# knixx_SW4_00.net
KiCad netlist of a schematic drawn in Altium Designer
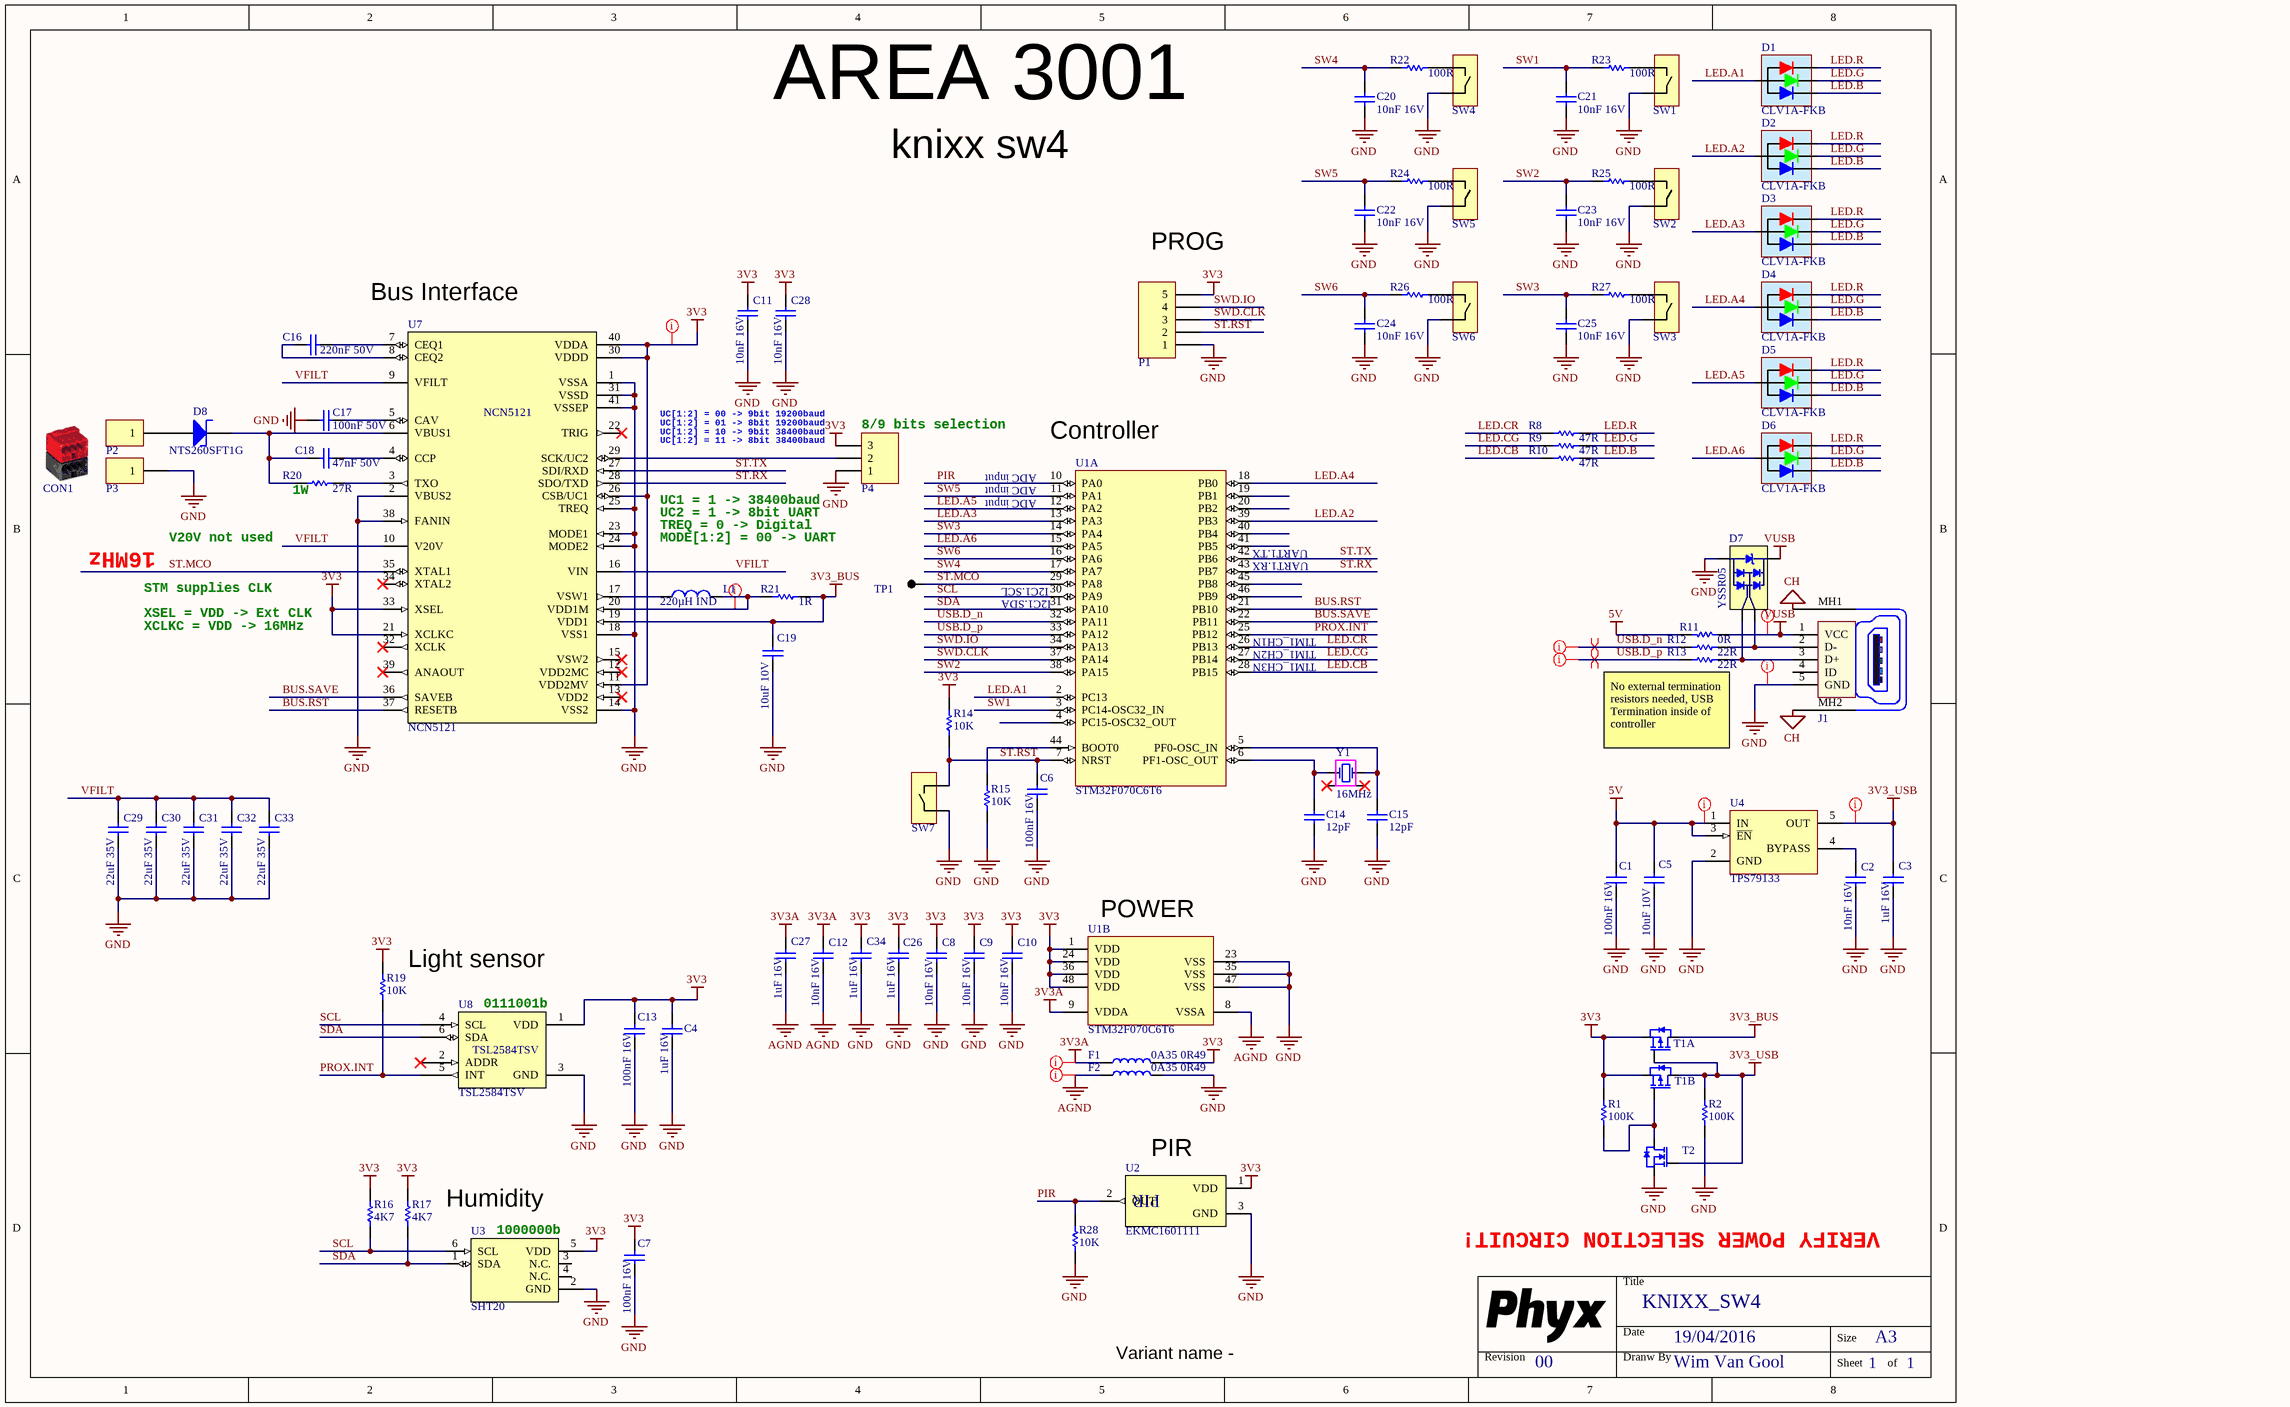
[diagram p0: knixx_SW4_00.SchDoc]

(export (version "E")
  (design (tool "Eeschema 10.0.6"))
  (components
    (comp (ref "C1")
      (value "100nF 16V")
      (footprint "C0402")
      (description "Capacitor Ceramic")
      (fields (field (name "Comment") "CAP_CERAMIC"))
      (libsource (lib "Phyx_Components") (part "CAP_CERAMIC"))
    )
    (comp (ref "C2")
      (value "10nF 16V")
      (footprint "C0402")
      (description "Capacitor Ceramic")
      (fields (field (name "Comment") "CAP_CERAMIC"))
      (libsource (lib "Phyx_Components") (part "CAP_CERAMIC"))
    )
    (comp (ref "C3")
      (value "1uF 16V")
      (footprint "C0603_N")
      (description "Capacitor Ceramic")
      (fields (field (name "Comment") "CAP_CERAMIC"))
      (libsource (lib "Phyx_Components") (part "CAP_CERAMIC"))
    )
    (comp (ref "C4")
      (value "1uF 16V")
      (footprint "C0603_N")
      (description "Capacitor Ceramic")
      (fields (field (name "Comment") "CAP_CERAMIC"))
      (libsource (lib "Phyx_Components") (part "CAP_CERAMIC"))
    )
    (comp (ref "C5")
      (value "10uF 10V")
      (footprint "C0805_N")
      (description "Capacitor Ceramic")
      (fields (field (name "Comment") "CAP_CERAMIC"))
      (libsource (lib "Phyx_Components") (part "CAP_CERAMIC"))
    )
    (comp (ref "C6")
      (value "100nF 16V")
      (footprint "C0402")
      (description "Capacitor Ceramic")
      (fields (field (name "Comment") "CAP_CERAMIC"))
      (libsource (lib "Phyx_Components") (part "CAP_CERAMIC"))
    )
    (comp (ref "C7")
      (value "100nF 16V")
      (footprint "C0402")
      (description "Capacitor Ceramic")
      (fields (field (name "Comment") "CAP_CERAMIC"))
      (libsource (lib "Phyx_Components") (part "CAP_CERAMIC"))
    )
    (comp (ref "C8")
      (value "10nF 16V")
      (footprint "C0402")
      (description "Capacitor Ceramic")
      (fields (field (name "Comment") "CAP_CERAMIC"))
      (libsource (lib "Phyx_Components") (part "CAP_CERAMIC"))
    )
    (comp (ref "C9")
      (value "10nF 16V")
      (footprint "C0402")
      (description "Capacitor Ceramic")
      (fields (field (name "Comment") "CAP_CERAMIC"))
      (libsource (lib "Phyx_Components") (part "CAP_CERAMIC"))
    )
    (comp (ref "C10")
      (value "10nF 16V")
      (footprint "C0402")
      (description "Capacitor Ceramic")
      (fields (field (name "Comment") "CAP_CERAMIC"))
      (libsource (lib "Phyx_Components") (part "CAP_CERAMIC"))
    )
    (comp (ref "C11")
      (value "10nF 16V")
      (footprint "C0402")
      (description "Capacitor Ceramic")
      (fields (field (name "Comment") "CAP_CERAMIC"))
      (libsource (lib "Phyx_Components") (part "CAP_CERAMIC"))
    )
    (comp (ref "C12")
      (value "10nF 16V")
      (footprint "C0402")
      (description "Capacitor Ceramic")
      (fields (field (name "Comment") "CAP_CERAMIC"))
      (libsource (lib "Phyx_Components") (part "CAP_CERAMIC"))
    )
    (comp (ref "C13")
      (value "100nF 16V")
      (footprint "C0402")
      (description "Capacitor Ceramic")
      (fields (field (name "Comment") "CAP_CERAMIC"))
      (libsource (lib "Phyx_Components") (part "CAP_CERAMIC"))
    )
    (comp (ref "C14")
      (value "12pF")
      (footprint "C0402")
      (description "Capacitor Ceramic")
      (fields (field (name "Comment") "CAP_CERAMIC"))
      (libsource (lib "Phyx_Components") (part "CAP_CERAMIC"))
    )
    (comp (ref "C15")
      (value "12pF")
      (footprint "C0402")
      (description "Capacitor Ceramic")
      (fields (field (name "Comment") "CAP_CERAMIC"))
      (libsource (lib "Phyx_Components") (part "CAP_CERAMIC"))
    )
    (comp (ref "C16")
      (value "220nF 50V")
      (footprint "C0805_N")
      (description "Capacitor Ceramic")
      (fields (field (name "Comment") "CAP_CERAMIC"))
      (libsource (lib "Phyx_Components") (part "CAP_CERAMIC"))
    )
    (comp (ref "C17")
      (value "100nF 50V")
      (footprint "C0603_N")
      (description "Capacitor Ceramic")
      (fields (field (name "Comment") "CAP_CERAMIC"))
      (libsource (lib "Phyx_Components") (part "CAP_CERAMIC"))
    )
    (comp (ref "C18")
      (value "47nF 50V")
      (footprint "C0603_N")
      (description "Capacitor Ceramic")
      (fields (field (name "Comment") "CAP_CERAMIC"))
      (libsource (lib "Phyx_Components") (part "CAP_CERAMIC"))
    )
    (comp (ref "C19")
      (value "10uF 10V")
      (footprint "C0805_N")
      (description "Capacitor Ceramic")
      (fields (field (name "Comment") "CAP_CERAMIC"))
      (libsource (lib "Phyx_Components") (part "CAP_CERAMIC"))
    )
    (comp (ref "C20")
      (value "10nF 16V")
      (footprint "C0402")
      (description "Capacitor Ceramic")
      (fields (field (name "Comment") "CAP_CERAMIC"))
      (libsource (lib "Phyx_Components") (part "CAP_CERAMIC"))
    )
    (comp (ref "C21")
      (value "10nF 16V")
      (footprint "C0402")
      (description "Capacitor Ceramic")
      (fields (field (name "Comment") "CAP_CERAMIC"))
      (libsource (lib "Phyx_Components") (part "CAP_CERAMIC"))
    )
    (comp (ref "C22")
      (value "10nF 16V")
      (footprint "C0402")
      (description "Capacitor Ceramic")
      (fields (field (name "Comment") "CAP_CERAMIC"))
      (libsource (lib "Phyx_Components") (part "CAP_CERAMIC"))
    )
    (comp (ref "C23")
      (value "10nF 16V")
      (footprint "C0402")
      (description "Capacitor Ceramic")
      (fields (field (name "Comment") "CAP_CERAMIC"))
      (libsource (lib "Phyx_Components") (part "CAP_CERAMIC"))
    )
    (comp (ref "C24")
      (value "10nF 16V")
      (footprint "C0402")
      (description "Capacitor Ceramic")
      (fields (field (name "Comment") "CAP_CERAMIC"))
      (libsource (lib "Phyx_Components") (part "CAP_CERAMIC"))
    )
    (comp (ref "C25")
      (value "10nF 16V")
      (footprint "C0402")
      (description "Capacitor Ceramic")
      (fields (field (name "Comment") "CAP_CERAMIC"))
      (libsource (lib "Phyx_Components") (part "CAP_CERAMIC"))
    )
    (comp (ref "C26")
      (value "1uF 16V")
      (footprint "C0603_N")
      (description "CAP # 1uF 16V 0603")
      (fields (field (name "Comment") "CAP_CERAMIC"))
      (libsource (lib "Phyx_Components") (part "CAP_CERAMIC"))
    )
    (comp (ref "C27")
      (value "1uF 16V")
      (footprint "C0603_N")
      (description "Capacitor Ceramic")
      (fields (field (name "Comment") "CAP_CERAMIC"))
      (libsource (lib "Phyx_Components") (part "CAP_CERAMIC"))
    )
    (comp (ref "C28")
      (value "10nF 16V")
      (footprint "C0402")
      (description "Capacitor Ceramic")
      (fields (field (name "Comment") "CAP_CERAMIC"))
      (libsource (lib "Phyx_Components") (part "CAP_CERAMIC"))
    )
    (comp (ref "C29")
      (value "22uF 35V")
      (footprint "C1206_N")
      (description "CAP # 22uF 35V 1206 X5R")
      (fields (field (name "Comment") "CAP_CERAMIC"))
      (libsource (lib "Phyx_Components") (part "CAP_CERAMIC"))
    )
    (comp (ref "C30")
      (value "22uF 35V")
      (footprint "C1206_N")
      (description "CAP # 22uF 35V 1206 X5R")
      (fields (field (name "Comment") "CAP_CERAMIC"))
      (libsource (lib "Phyx_Components") (part "CAP_CERAMIC"))
    )
    (comp (ref "C31")
      (value "22uF 35V")
      (footprint "C1206_N")
      (description "CAP # 22uF 35V 1206 X5R")
      (fields (field (name "Comment") "CAP_CERAMIC"))
      (libsource (lib "Phyx_Components") (part "CAP_CERAMIC"))
    )
    (comp (ref "C32")
      (value "22uF 35V")
      (footprint "C1206_N")
      (description "CAP # 22uF 35V 1206 X5R")
      (fields (field (name "Comment") "CAP_CERAMIC"))
      (libsource (lib "Phyx_Components") (part "CAP_CERAMIC"))
    )
    (comp (ref "C33")
      (value "22uF 35V")
      (footprint "C1206_N")
      (description "CAP # 22uF 35V 1206 X5R")
      (fields (field (name "Comment") "CAP_CERAMIC"))
      (libsource (lib "Phyx_Components") (part "CAP_CERAMIC"))
    )
    (comp (ref "C34")
      (value "1uF 16V")
      (footprint "C0603_N")
      (description "Capacitor Ceramic")
      (fields (field (name "Comment") "CAP_CERAMIC"))
      (libsource (lib "Phyx_Components") (part "CAP_CERAMIC"))
    )
    (comp (ref "CON1")
      (value "CONNECTOR FOR EIB APPLICATIONS PUSH-WIRE® CONNECTION")
      (footprint "WAGO_243-211")
      (libsource (lib "Phyx_Components") (part "WAGO_243-211"))
    )
    (comp (ref "D1")
      (value "CLV1A-FKB")
      (footprint "Cree_CLV1A-FKB")
      (description "=Description")
      (fields (field (name "Comment") "PLCC2 general purpose RGB LED Cree CLV1A-FKB"))
      (libsource (lib "Phyx_Components") (part "Cree_CLV1A-FKB"))
    )
    (comp (ref "D2")
      (value "CLV1A-FKB")
      (footprint "Cree_CLV1A-FKB")
      (description "=Description")
      (fields (field (name "Comment") "PLCC2 general purpose RGB LED Cree CLV1A-FKB"))
      (libsource (lib "Phyx_Components") (part "Cree_CLV1A-FKB"))
    )
    (comp (ref "D3")
      (value "CLV1A-FKB")
      (footprint "Cree_CLV1A-FKB")
      (description "=Description")
      (fields (field (name "Comment") "PLCC2 general purpose RGB LED Cree CLV1A-FKB"))
      (libsource (lib "Phyx_Components") (part "Cree_CLV1A-FKB"))
    )
    (comp (ref "D4")
      (value "CLV1A-FKB")
      (footprint "Cree_CLV1A-FKB")
      (description "=Description")
      (fields (field (name "Comment") "PLCC2 general purpose RGB LED Cree CLV1A-FKB"))
      (libsource (lib "Phyx_Components") (part "Cree_CLV1A-FKB"))
    )
    (comp (ref "D5")
      (value "CLV1A-FKB")
      (footprint "Cree_CLV1A-FKB")
      (description "=Description")
      (fields (field (name "Comment") "PLCC2 general purpose RGB LED Cree CLV1A-FKB"))
      (libsource (lib "Phyx_Components") (part "Cree_CLV1A-FKB"))
    )
    (comp (ref "D6")
      (value "CLV1A-FKB")
      (footprint "Cree_CLV1A-FKB")
      (description "=Description")
      (fields (field (name "Comment") "PLCC2 general purpose RGB LED Cree CLV1A-FKB"))
      (libsource (lib "Phyx_Components") (part "Cree_CLV1A-FKB"))
    )
    (comp (ref "D7")
      (value "YSSR05")
      (footprint "SOT-143")
      (description "=Description")
      (fields (field (name "Comment") "Low Capacitanse TVS Diode array"))
      (libsource (lib "Phyx_Components") (part "YSSR05"))
    )
    (comp (ref "D8")
      (value "NTS260SFT1G")
      (footprint "ON_SOD-123FL")
      (description "=Description")
      (fields (field (name "Comment") "NTS260SFT1G  Schottky Rectifier, Single, 60 V, 2 A, SOD-123, 650 mV"))
      (libsource (lib "Phyx_Components") (part "Schottky_21"))
    )
    (comp (ref "F1")
      (value "0A35 0R49")
      (footprint "L0402")
      (fields (field (name "Comment") "BLM15AX102SN1D"))
      (libsource (lib "Phyx_Components") (part "FERRITE"))
    )
    (comp (ref "F2")
      (value "0A35 0R49")
      (footprint "L0402")
      (fields (field (name "Comment") "BLM15AX102SN1D"))
      (libsource (lib "Phyx_Components") (part "FERRITE"))
    )
    (comp (ref "J1")
      (value "Vertical Micro USB B 614105150721")
      (footprint "WE_614105150721")
      (libsource (lib "Phyx_Components") (part "WE_614105150721"))
    )
    (comp (ref "L1")
      (value "220µH IND")
      (footprint "IND_6045")
      (fields (field (name "Comment") "220µH INDUCTOR"))
      (libsource (lib "Phyx_Components") (part "INDUCTOR"))
    )
    (comp (ref "P1")
      (value "Header 1.0mm Shrouded 5")
      (footprint "WE_665305124022")
      (libsource (lib "Phyx_Components") (part "Header 5"))
    )
    (comp (ref "P2")
      (value "SOLDER PIN FOR PCBS UP TO 2 MM")
      (footprint "WAGO_243-131")
      (libsource (lib "Phyx_Components") (part "Header 1"))
    )
    (comp (ref "P3")
      (value "SOLDER PIN FOR PCBS UP TO 2 MM")
      (footprint "WAGO_243-131")
      (libsource (lib "Phyx_Components") (part "Header 1"))
    )
    (comp (ref "P4")
      (value "3 pin Solder SW Circular 1mm")
      (footprint "SOLDER_SW_C_1MM_3")
      (libsource (lib "Phyx_Components") (part "Header 3"))
    )
    (comp (ref "R1")
      (value "100K")
      (footprint "R0402")
      (fields (field (name "Comment") "RESISTOR"))
      (libsource (lib "Phyx_Components") (part "RESISTOR"))
    )
    (comp (ref "R2")
      (value "100K")
      (footprint "R0402")
      (fields (field (name "Comment") "RESISTOR"))
      (libsource (lib "Phyx_Components") (part "RESISTOR"))
    )
    (comp (ref "R8")
      (value "47R")
      (footprint "R0402")
      (fields (field (name "Comment") "RESISTOR"))
      (libsource (lib "Phyx_Components") (part "RESISTOR"))
    )
    (comp (ref "R9")
      (value "47R")
      (footprint "R0402")
      (fields (field (name "Comment") "RESISTOR"))
      (libsource (lib "Phyx_Components") (part "RESISTOR"))
    )
    (comp (ref "R10")
      (value "47R")
      (footprint "R0402")
      (fields (field (name "Comment") "RESISTOR"))
      (libsource (lib "Phyx_Components") (part "RESISTOR"))
    )
    (comp (ref "R11")
      (value "0R")
      (footprint "R0603_N")
      (fields (field (name "Comment") "RESISTOR"))
      (libsource (lib "Phyx_Components") (part "RESISTOR"))
    )
    (comp (ref "R12")
      (value "22R")
      (footprint "R0402")
      (fields (field (name "Comment") "RESISTOR"))
      (libsource (lib "Phyx_Components") (part "RESISTOR"))
    )
    (comp (ref "R13")
      (value "22R")
      (footprint "R0402")
      (fields (field (name "Comment") "RESISTOR"))
      (libsource (lib "Phyx_Components") (part "RESISTOR"))
    )
    (comp (ref "R14")
      (value "10K")
      (footprint "R0402")
      (fields (field (name "Comment") "RESISTOR"))
      (libsource (lib "Phyx_Components") (part "RESISTOR"))
    )
    (comp (ref "R15")
      (value "10K")
      (footprint "R0402")
      (fields (field (name "Comment") "RESISTOR"))
      (libsource (lib "Phyx_Components") (part "RESISTOR"))
    )
    (comp (ref "R16")
      (value "4K7")
      (footprint "R0402")
      (fields (field (name "Comment") "RESISTOR"))
      (libsource (lib "Phyx_Components") (part "RESISTOR"))
    )
    (comp (ref "R17")
      (value "4K7")
      (footprint "R0402")
      (fields (field (name "Comment") "RESISTOR"))
      (libsource (lib "Phyx_Components") (part "RESISTOR"))
    )
    (comp (ref "R19")
      (value "10K")
      (footprint "R0402")
      (fields (field (name "Comment") "RESISTOR"))
      (libsource (lib "Phyx_Components") (part "RESISTOR"))
    )
    (comp (ref "R20")
      (value "27R")
      (footprint "R2512")
      (fields (field (name "Comment") "RESISTOR"))
      (libsource (lib "Phyx_Components") (part "RESISTOR"))
    )
    (comp (ref "R21")
      (value "1R")
      (footprint "R0402")
      (fields (field (name "Comment") "RESISTOR"))
      (libsource (lib "Phyx_Components") (part "RESISTOR"))
    )
    (comp (ref "R22")
      (value "100R")
      (footprint "R0402")
      (fields (field (name "Comment") "RESISTOR"))
      (libsource (lib "Phyx_Components") (part "RESISTOR"))
    )
    (comp (ref "R23")
      (value "100R")
      (footprint "R0402")
      (fields (field (name "Comment") "RESISTOR"))
      (libsource (lib "Phyx_Components") (part "RESISTOR"))
    )
    (comp (ref "R24")
      (value "100R")
      (footprint "R0402")
      (fields (field (name "Comment") "RESISTOR"))
      (libsource (lib "Phyx_Components") (part "RESISTOR"))
    )
    (comp (ref "R25")
      (value "100R")
      (footprint "R0402")
      (fields (field (name "Comment") "RESISTOR"))
      (libsource (lib "Phyx_Components") (part "RESISTOR"))
    )
    (comp (ref "R26")
      (value "100R")
      (footprint "R0402")
      (fields (field (name "Comment") "RESISTOR"))
      (libsource (lib "Phyx_Components") (part "RESISTOR"))
    )
    (comp (ref "R27")
      (value "100R")
      (footprint "R0402")
      (fields (field (name "Comment") "RESISTOR"))
      (libsource (lib "Phyx_Components") (part "RESISTOR"))
    )
    (comp (ref "R28")
      (value "10K")
      (footprint "R0402")
      (fields (field (name "Comment") "RESISTOR"))
      (libsource (lib "Phyx_Components") (part "RESISTOR"))
    )
    (comp (ref "SW1")
      (value "Sealed Tact Switch for SMT 6,2x6,2x7,7")
      (footprint "CK_KSC6xxJ")
      (libsource (lib "Phyx_Components") (part "SW_TACT"))
    )
    (comp (ref "SW2")
      (value "Sealed Tact Switch for SMT 6,2x6,2x7,7")
      (footprint "CK_KSC6xxJ")
      (libsource (lib "Phyx_Components") (part "SW_TACT"))
    )
    (comp (ref "SW3")
      (value "Sealed Tact Switch for SMT 6,2x6,2x7,7")
      (footprint "CK_KSC6xxJ")
      (libsource (lib "Phyx_Components") (part "SW_TACT"))
    )
    (comp (ref "SW4")
      (value "Sealed Tact Switch for SMT 6,2x6,2x7,7")
      (footprint "CK_KSC6xxJ")
      (libsource (lib "Phyx_Components") (part "SW_TACT"))
    )
    (comp (ref "SW5")
      (value "Sealed Tact Switch for SMT 6,2x6,2x7,7")
      (footprint "CK_KSC6xxJ")
      (libsource (lib "Phyx_Components") (part "SW_TACT"))
    )
    (comp (ref "SW6")
      (value "Sealed Tact Switch for SMT 6,2x6,2x7,7")
      (footprint "CK_KSC6xxJ")
      (libsource (lib "Phyx_Components") (part "SW_TACT"))
    )
    (comp (ref "SW7") (value "LP SMD tact sw") (footprint "CK_KMR4") (libsource (lib "") (part "SW_TACT_1")))
    (comp (ref "T1")
      (value "0.8A Dual P-Ch MOSGET Vgs -1.2")
      (footprint "SOT-363")
      (description "=Description")
      (libsource (lib "Phyx_Components") (part "P_MOSFET_S1G1D2S2G2D1"))
    )
    (comp (ref "T2")
      (value "0.2A N-Ch MOSFET Vgs 3.2")
      (footprint "SOT23-3")
      (libsource (lib "Phyx_Components") (part "N_MOSFET_GSD"))
    )
    (comp (ref "TP1")
      (value "TEST_PAD")
      (footprint "TP_0.8mm")
      (libsource (lib "Phyx_Components") (part "TEST_PAD"))
    )
    (comp (ref "U1")
      (value "STM32F070C6T6")
      (footprint "STM_LQFP48_N")
      (description "=Description")
      (fields
        (field (name "PARTNUMBER") "STM32F373CCT6")
        (field (name "Comment") "Entry-level ARM Cortex-M0 Value line MCU with up to 32 Kbytes Flash, 48 MHz CPU, USB")
      )
      (libsource (lib "Phyx_Components") (part "STM32F070C6T6"))
    )
    (comp (ref "U2")
      (value "EKMC1601111")
      (footprint "PAN_EKMC1601111")
      (description "=Description")
      (fields (field (name "Comment") "PIR 5m White"))
      (libsource (lib "Phyx_Components") (part "EKMC160x111x"))
    )
    (comp (ref "U3")
      (value "SHT20")
      (footprint "SNS_DFN6")
      (description "=Description")
      (fields (field (name "Comment") "Sensirion SHT20 temperature and humidity sensor I2C"))
      (libsource (lib "Phyx_Components") (part "SHT2x"))
    )
    (comp (ref "U4")
      (value "TPS79133")
      (footprint "TI_DBV_R-PDSO-G5")
      (description "=Description")
      (fields (field (name "Comment") "3V3 100mA Ultra Low Noise LDO"))
      (libsource (lib "Phyx_Components") (part "TPS791xx"))
    )
    (comp (ref "U7")
      (value "NCN5121")
      (footprint "ONS_QFN40_6x6")
      (description "=Description")
      (fields (field (name "Comment") "KNX Transceiver for Twisted Pair Networks"))
      (libsource (lib "Phyx_Components") (part "NCN5121"))
    )
    (comp (ref "U8")
      (value "TSL2584TSV")
      (footprint "AMS_6TSV")
      (description "=Description")
      (fields (field (name "Comment") "TSL2584TSV Light-to-Digital Device"))
      (libsource (lib "Phyx_Components") (part "TSL2584TSV"))
    )
    (comp (ref "Y1")
      (value "16MHz")
      (footprint "ABMM2")
      (description "XTAL # 16Mhz ABMM2")
      (fields (field (name "Comment") "16MHZ ABMM2"))
      (libsource (lib "Phyx_Components") (part "XTAL_4"))
    )
  )
  (nets
    (net (code "1") (name "/BUS.RST") (class "Default")
      (node (ref "U1") (pin "21") (pinfunction "PB10_21") (pintype "bidirectional"))
      (node (ref "U7") (pin "37") (pinfunction "RESETB_37") (pintype "output"))
    )
    (net (code "2") (name "/BUS.SAVE") (class "Default")
      (node (ref "U1") (pin "22") (pinfunction "PB11_22") (pintype "bidirectional"))
      (node (ref "U7") (pin "36") (pinfunction "SAVEB_36") (pintype "output"))
    )
    (net (code "3") (name "/LED.A1") (class "Default")
      (node (ref "D1") (pin "2") (pinfunction "A_2") (pintype "passive"))
      (node (ref "U1") (pin "2") (pinfunction "PC13_2") (pintype "bidirectional"))
    )
    (net (code "4") (name "/LED.A2") (class "Default")
      (node (ref "D2") (pin "2") (pinfunction "A_2") (pintype "passive"))
      (node (ref "U1") (pin "39") (pinfunction "PB3_39") (pintype "bidirectional"))
    )
    (net (code "5") (name "/LED.A3") (class "Default")
      (node (ref "D3") (pin "2") (pinfunction "A_2") (pintype "passive"))
      (node (ref "U1") (pin "13") (pinfunction "PA3_13") (pintype "bidirectional"))
    )
    (net (code "6") (name "/LED.A4") (class "Default")
      (node (ref "D4") (pin "2") (pinfunction "A_2") (pintype "passive"))
      (node (ref "U1") (pin "18") (pinfunction "PB0_18") (pintype "bidirectional"))
    )
    (net (code "7") (name "/LED.A5") (class "Default")
      (node (ref "D5") (pin "2") (pinfunction "A_2") (pintype "passive"))
      (node (ref "U1") (pin "12") (pinfunction "PA2_12") (pintype "bidirectional"))
    )
    (net (code "8") (name "/LED.A6") (class "Default")
      (node (ref "D6") (pin "2") (pinfunction "A_2") (pintype "passive"))
      (node (ref "U1") (pin "15") (pinfunction "PA5_15") (pintype "bidirectional"))
    )
    (net (code "9") (name "/LED.B") (class "Default")
      (node (ref "D1") (pin "3") (pinfunction "BC_3") (pintype "passive"))
      (node (ref "D2") (pin "3") (pinfunction "BC_3") (pintype "passive"))
      (node (ref "D3") (pin "3") (pinfunction "BC_3") (pintype "passive"))
      (node (ref "D4") (pin "3") (pinfunction "BC_3") (pintype "passive"))
      (node (ref "D5") (pin "3") (pinfunction "BC_3") (pintype "passive"))
      (node (ref "D6") (pin "3") (pinfunction "BC_3") (pintype "passive"))
      (node (ref "R10") (pin "1") (pinfunction "1_1") (pintype "passive"))
    )
    (net (code "10") (name "/LED.CB") (class "Default")
      (node (ref "R10") (pin "2") (pinfunction "2_2") (pintype "passive"))
      (node (ref "U1") (pin "28") (pinfunction "PB15_28") (pintype "bidirectional"))
    )
    (net (code "11") (name "/LED.CG") (class "Default")
      (node (ref "R9") (pin "2") (pinfunction "2_2") (pintype "passive"))
      (node (ref "U1") (pin "27") (pinfunction "PB14_27") (pintype "bidirectional"))
    )
    (net (code "12") (name "/LED.CR") (class "Default")
      (node (ref "R8") (pin "2") (pinfunction "2_2") (pintype "passive"))
      (node (ref "U1") (pin "26") (pinfunction "PB13_26") (pintype "bidirectional"))
    )
    (net (code "13") (name "/LED.G") (class "Default")
      (node (ref "D1") (pin "4") (pinfunction "GC_4") (pintype "passive"))
      (node (ref "D2") (pin "4") (pinfunction "GC_4") (pintype "passive"))
      (node (ref "D3") (pin "4") (pinfunction "GC_4") (pintype "passive"))
      (node (ref "D4") (pin "4") (pinfunction "GC_4") (pintype "passive"))
      (node (ref "D5") (pin "4") (pinfunction "GC_4") (pintype "passive"))
      (node (ref "D6") (pin "4") (pinfunction "GC_4") (pintype "passive"))
      (node (ref "R9") (pin "1") (pinfunction "1_1") (pintype "passive"))
    )
    (net (code "14") (name "/LED.R") (class "Default")
      (node (ref "D1") (pin "1") (pinfunction "RC_1") (pintype "passive"))
      (node (ref "D2") (pin "1") (pinfunction "RC_1") (pintype "passive"))
      (node (ref "D3") (pin "1") (pinfunction "RC_1") (pintype "passive"))
      (node (ref "D4") (pin "1") (pinfunction "RC_1") (pintype "passive"))
      (node (ref "D5") (pin "1") (pinfunction "RC_1") (pintype "passive"))
      (node (ref "D6") (pin "1") (pinfunction "RC_1") (pintype "passive"))
      (node (ref "R8") (pin "1") (pinfunction "1_1") (pintype "passive"))
    )
    (net (code "15") (name "/PIR") (class "Default")
      (node (ref "R28") (pin "1") (pinfunction "1_1") (pintype "passive"))
      (node (ref "U1") (pin "10") (pinfunction "PA0_10") (pintype "bidirectional"))
      (node (ref "U2") (pin "2") (pinfunction "OUT_2") (pintype "output"))
    )
    (net (code "16") (name "/PROX.INT") (class "Default")
      (node (ref "R19") (pin "2") (pinfunction "2_2") (pintype "passive"))
      (node (ref "U1") (pin "25") (pinfunction "PB12_25") (pintype "bidirectional"))
      (node (ref "U8") (pin "5") (pinfunction "INT_5") (pintype "output"))
    )
    (net (code "17") (name "/SCL") (class "Default")
      (node (ref "R16") (pin "2") (pinfunction "2_2") (pintype "passive"))
      (node (ref "U1") (pin "30") (pinfunction "PA9_30") (pintype "bidirectional"))
      (node (ref "U3") (pin "6") (pinfunction "SCL_6") (pintype "input"))
      (node (ref "U8") (pin "4") (pinfunction "SCL_4") (pintype "input"))
    )
    (net (code "18") (name "/SDA") (class "Default")
      (node (ref "R17") (pin "2") (pinfunction "2_2") (pintype "passive"))
      (node (ref "U1") (pin "31") (pinfunction "PA10_31") (pintype "bidirectional"))
      (node (ref "U3") (pin "1") (pinfunction "SDA_1") (pintype "bidirectional"))
      (node (ref "U8") (pin "6") (pinfunction "SDA_6") (pintype "bidirectional"))
    )
    (net (code "19") (name "/ST.MCO") (class "Default")
      (node (ref "TP1") (pin "1") (pinfunction "1_1") (pintype "passive"))
      (node (ref "U1") (pin "29") (pinfunction "PA8_29") (pintype "bidirectional"))
      (node (ref "U7") (pin "35") (pinfunction "XTAL1_35") (pintype "bidirectional"))
    )
    (net (code "20") (name "/ST.RST") (class "Default")
      (node (ref "C6") (pin "1") (pinfunction "1_1") (pintype "passive"))
      (node (ref "P1") (pin "2") (pinfunction "2_2") (pintype "passive"))
      (node (ref "R14") (pin "2") (pinfunction "2_2") (pintype "passive"))
      (node (ref "SW7") (pin "1") (pinfunction "1_1") (pintype "passive"))
      (node (ref "U1") (pin "7") (pinfunction "NRST_7") (pintype "bidirectional"))
    )
    (net (code "21") (name "/ST.RX") (class "Default")
      (node (ref "U1") (pin "43") (pinfunction "PB7_43") (pintype "bidirectional"))
      (node (ref "U7") (pin "28") (pinfunction "SDO/TXD_28") (pintype "output"))
    )
    (net (code "22") (name "/ST.TX") (class "Default")
      (node (ref "U1") (pin "42") (pinfunction "PB6_42") (pintype "bidirectional"))
      (node (ref "U7") (pin "27") (pinfunction "SDI/RXD_27") (pintype "input"))
    )
    (net (code "23") (name "/SW1") (class "Default")
      (node (ref "C21") (pin "1") (pinfunction "1_1") (pintype "passive"))
      (node (ref "R23") (pin "2") (pinfunction "2_2") (pintype "passive"))
      (node (ref "U1") (pin "3") (pinfunction "PC14-OSC32_IN_3") (pintype "bidirectional"))
    )
    (net (code "24") (name "/SW2") (class "Default")
      (node (ref "C23") (pin "1") (pinfunction "1_1") (pintype "passive"))
      (node (ref "R25") (pin "2") (pinfunction "2_2") (pintype "passive"))
      (node (ref "U1") (pin "38") (pinfunction "PA15_38") (pintype "bidirectional"))
    )
    (net (code "25") (name "/SW3") (class "Default")
      (node (ref "C25") (pin "1") (pinfunction "1_1") (pintype "passive"))
      (node (ref "R27") (pin "2") (pinfunction "2_2") (pintype "passive"))
      (node (ref "U1") (pin "14") (pinfunction "PA4_14") (pintype "bidirectional"))
    )
    (net (code "26") (name "/SW4") (class "Default")
      (node (ref "C20") (pin "1") (pinfunction "1_1") (pintype "passive"))
      (node (ref "R22") (pin "2") (pinfunction "2_2") (pintype "passive"))
      (node (ref "U1") (pin "17") (pinfunction "PA7_17") (pintype "bidirectional"))
    )
    (net (code "27") (name "/SW5") (class "Default")
      (node (ref "C22") (pin "1") (pinfunction "1_1") (pintype "passive"))
      (node (ref "R24") (pin "2") (pinfunction "2_2") (pintype "passive"))
      (node (ref "U1") (pin "11") (pinfunction "PA1_11") (pintype "bidirectional"))
    )
    (net (code "28") (name "/SW6") (class "Default")
      (node (ref "C24") (pin "1") (pinfunction "1_1") (pintype "passive"))
      (node (ref "R26") (pin "2") (pinfunction "2_2") (pintype "passive"))
      (node (ref "U1") (pin "16") (pinfunction "PA6_16") (pintype "bidirectional"))
    )
    (net (code "29") (name "/SWD.CLK") (class "Default")
      (node (ref "P1") (pin "3") (pinfunction "3_3") (pintype "passive"))
      (node (ref "U1") (pin "37") (pinfunction "PA14_37") (pintype "bidirectional"))
    )
    (net (code "30") (name "/SWD.IO") (class "Default")
      (node (ref "P1") (pin "4") (pinfunction "4_4") (pintype "passive"))
      (node (ref "U1") (pin "34") (pinfunction "PA13_34") (pintype "bidirectional"))
    )
    (net (code "31") (name "/USB.D_n") (class "Default")
      (node (ref "R12") (pin "2") (pinfunction "2_2") (pintype "passive"))
      (node (ref "U1") (pin "32") (pinfunction "PA11_32") (pintype "bidirectional"))
    )
    (net (code "32") (name "/USB.D_p") (class "Default")
      (node (ref "R13") (pin "2") (pinfunction "2_2") (pintype "passive"))
      (node (ref "U1") (pin "33") (pinfunction "PA12_33") (pintype "bidirectional"))
    )
    (net (code "33") (name "/VFILT") (class "Default")
      (node (ref "C29") (pin "1") (pinfunction "1_1") (pintype "passive"))
      (node (ref "C30") (pin "1") (pinfunction "1_1") (pintype "passive"))
      (node (ref "C31") (pin "1") (pinfunction "1_1") (pintype "passive"))
      (node (ref "C32") (pin "1") (pinfunction "1_1") (pintype "passive"))
      (node (ref "C33") (pin "1") (pinfunction "1_1") (pintype "passive"))
      (node (ref "U7") (pin "10") (pinfunction "V20V_10") (pintype "power_in"))
      (node (ref "U7") (pin "16") (pinfunction "VIN_16") (pintype "power_in"))
      (node (ref "U7") (pin "9") (pinfunction "VFILT_9") (pintype "power_in"))
    )
    (net (code "34") (name "3V3") (class "Default")
      (node (ref "C10") (pin "1") (pinfunction "1_1") (pintype "passive"))
      (node (ref "C11") (pin "1") (pinfunction "1_1") (pintype "passive"))
      (node (ref "C13") (pin "1") (pinfunction "1_1") (pintype "passive"))
      (node (ref "C26") (pin "1") (pinfunction "1_1") (pintype "passive"))
      (node (ref "C28") (pin "1") (pinfunction "1_1") (pintype "passive"))
      (node (ref "C34") (pin "1") (pinfunction "1_1") (pintype "passive"))
      (node (ref "C4") (pin "1") (pinfunction "1_1") (pintype "passive"))
      (node (ref "C7") (pin "1") (pinfunction "1_1") (pintype "passive"))
      (node (ref "C8") (pin "1") (pinfunction "1_1") (pintype "passive"))
      (node (ref "C9") (pin "1") (pinfunction "1_1") (pintype "passive"))
      (node (ref "F1") (pin "2") (pinfunction "2_2") (pintype "passive"))
      (node (ref "P1") (pin "5") (pinfunction "5_5") (pintype "passive"))
      (node (ref "P4") (pin "3") (pinfunction "3_3") (pintype "passive"))
      (node (ref "R1") (pin "1") (pinfunction "1_1") (pintype "passive"))
      (node (ref "R14") (pin "1") (pinfunction "1_1") (pintype "passive"))
      (node (ref "R16") (pin "1") (pinfunction "1_1") (pintype "passive"))
      (node (ref "R17") (pin "1") (pinfunction "1_1") (pintype "passive"))
      (node (ref "R19") (pin "1") (pinfunction "1_1") (pintype "passive"))
      (node (ref "T1") (pin "1") (pinfunction "S_1") (pintype "passive"))
      (node (ref "T1") (pin "4") (pinfunction "S_4") (pintype "passive"))
      (node (ref "U1") (pin "1") (pinfunction "VDD_1") (pintype "power_in"))
      (node (ref "U1") (pin "24") (pinfunction "VDD_24") (pintype "power_in"))
      (node (ref "U1") (pin "36") (pinfunction "VDD_36") (pintype "power_in"))
      (node (ref "U1") (pin "48") (pinfunction "VDD_48") (pintype "power_in"))
      (node (ref "U2") (pin "1") (pinfunction "VDD_1") (pintype "power_in"))
      (node (ref "U3") (pin "5") (pinfunction "VDD_5") (pintype "power_in"))
      (node (ref "U7") (pin "11") (pinfunction "VDD2MV_11") (pintype "input"))
      (node (ref "U7") (pin "21") (pinfunction "XCLKC_21") (pintype "input"))
      (node (ref "U7") (pin "26") (pinfunction "CSB/UC1_26") (pintype "bidirectional"))
      (node (ref "U7") (pin "30") (pinfunction "VDDD_30") (pintype "power_in"))
      (node (ref "U7") (pin "33") (pinfunction "XSEL_33") (pintype "input"))
      (node (ref "U7") (pin "40") (pinfunction "VDDA_40") (pintype "power_in"))
      (node (ref "U8") (pin "1") (pinfunction "VDD_1") (pintype "passive"))
    )
    (net (code "35") (name "3V3A") (class "Default")
      (node (ref "C12") (pin "1") (pinfunction "1_1") (pintype "passive"))
      (node (ref "C27") (pin "1") (pinfunction "1_1") (pintype "passive"))
      (node (ref "F1") (pin "1") (pinfunction "1_1") (pintype "passive"))
      (node (ref "U1") (pin "9") (pinfunction "VDDA_9") (pintype "power_in"))
    )
    (net (code "36") (name "3V3_BUS") (class "Default")
      (node (ref "C19") (pin "1") (pinfunction "1_1") (pintype "passive"))
      (node (ref "R21") (pin "1") (pinfunction "1_1") (pintype "passive"))
      (node (ref "T1") (pin "6") (pinfunction "D_6") (pintype "passive"))
      (node (ref "U7") (pin "19") (pinfunction "VDD1_19") (pintype "input"))
    )
    (net (code "37") (name "3V3_USB") (class "Default")
      (node (ref "C3") (pin "1") (pinfunction "1_1") (pintype "passive"))
      (node (ref "R2") (pin "1") (pinfunction "1_1") (pintype "passive"))
      (node (ref "T1") (pin "2") (pinfunction "G_2") (pintype "passive"))
      (node (ref "T1") (pin "3") (pinfunction "D_3") (pintype "passive"))
      (node (ref "T2") (pin "1") (pinfunction "G_1") (pintype "passive"))
      (node (ref "U4") (pin "5") (pinfunction "OUT_5") (pintype "power_in"))
    )
    (net (code "38") (name "5V") (class "Default")
      (node (ref "C1") (pin "1") (pinfunction "1_1") (pintype "passive"))
      (node (ref "C5") (pin "1") (pinfunction "1_1") (pintype "passive"))
      (node (ref "R11") (pin "2") (pinfunction "2_2") (pintype "passive"))
      (node (ref "U4") (pin "1") (pinfunction "IN_1") (pintype "power_in"))
      (node (ref "U4") (pin "3") (pinfunction "~{EN}_3") (pintype "input"))
    )
    (net (code "39") (name "AGND") (class "Default")
      (node (ref "C12") (pin "2") (pinfunction "2_2") (pintype "passive"))
      (node (ref "C27") (pin "2") (pinfunction "2_2") (pintype "passive"))
      (node (ref "F2") (pin "1") (pinfunction "1_1") (pintype "passive"))
      (node (ref "U1") (pin "8") (pinfunction "VSSA_8") (pintype "power_in"))
    )
    (net (code "40") (name "CH") (class "Default")
      (node (ref "J1") (pin "MH1") (pinfunction "MH1_MH1") (pintype "passive"))
      (node (ref "J1") (pin "MH2") (pinfunction "MH2_MH2") (pintype "passive"))
    )
    (net (code "41") (name "GND") (class "Default")
      (node (ref "C1") (pin "2") (pinfunction "2_2") (pintype "passive"))
      (node (ref "C10") (pin "2") (pinfunction "2_2") (pintype "passive"))
      (node (ref "C11") (pin "2") (pinfunction "2_2") (pintype "passive"))
      (node (ref "C13") (pin "2") (pinfunction "2_2") (pintype "passive"))
      (node (ref "C14") (pin "2") (pinfunction "2_2") (pintype "passive"))
      (node (ref "C15") (pin "2") (pinfunction "2_2") (pintype "passive"))
      (node (ref "C17") (pin "2") (pinfunction "2_2") (pintype "passive"))
      (node (ref "C19") (pin "2") (pinfunction "2_2") (pintype "passive"))
      (node (ref "C2") (pin "2") (pinfunction "2_2") (pintype "passive"))
      (node (ref "C20") (pin "2") (pinfunction "2_2") (pintype "passive"))
      (node (ref "C21") (pin "2") (pinfunction "2_2") (pintype "passive"))
      (node (ref "C22") (pin "2") (pinfunction "2_2") (pintype "passive"))
      (node (ref "C23") (pin "2") (pinfunction "2_2") (pintype "passive"))
      (node (ref "C24") (pin "2") (pinfunction "2_2") (pintype "passive"))
      (node (ref "C25") (pin "2") (pinfunction "2_2") (pintype "passive"))
      (node (ref "C26") (pin "2") (pinfunction "2_2") (pintype "passive"))
      (node (ref "C28") (pin "2") (pinfunction "2_2") (pintype "passive"))
      (node (ref "C29") (pin "2") (pinfunction "2_2") (pintype "passive"))
      (node (ref "C3") (pin "2") (pinfunction "2_2") (pintype "passive"))
      (node (ref "C30") (pin "2") (pinfunction "2_2") (pintype "passive"))
      (node (ref "C31") (pin "2") (pinfunction "2_2") (pintype "passive"))
      (node (ref "C32") (pin "2") (pinfunction "2_2") (pintype "passive"))
      (node (ref "C33") (pin "2") (pinfunction "2_2") (pintype "passive"))
      (node (ref "C34") (pin "2") (pinfunction "2_2") (pintype "passive"))
      (node (ref "C4") (pin "2") (pinfunction "2_2") (pintype "passive"))
      (node (ref "C5") (pin "2") (pinfunction "2_2") (pintype "passive"))
      (node (ref "C6") (pin "2") (pinfunction "2_2") (pintype "passive"))
      (node (ref "C7") (pin "2") (pinfunction "2_2") (pintype "passive"))
      (node (ref "C8") (pin "2") (pinfunction "2_2") (pintype "passive"))
      (node (ref "C9") (pin "2") (pinfunction "2_2") (pintype "passive"))
      (node (ref "D7") (pin "1") (pinfunction "1_1") (pintype "passive"))
      (node (ref "F2") (pin "2") (pinfunction "2_2") (pintype "passive"))
      (node (ref "J1") (pin "5") (pinfunction "GND_5") (pintype "passive"))
      (node (ref "P1") (pin "1") (pinfunction "1_1") (pintype "passive"))
      (node (ref "P3") (pin "1") (pinfunction "1_1") (pintype "passive"))
      (node (ref "P4") (pin "1") (pinfunction "1_1") (pintype "passive"))
      (node (ref "R15") (pin "2") (pinfunction "2_2") (pintype "passive"))
      (node (ref "R2") (pin "2") (pinfunction "2_2") (pintype "passive"))
      (node (ref "R28") (pin "2") (pinfunction "2_2") (pintype "passive"))
      (node (ref "SW1") (pin "2") (pinfunction "2_2") (pintype "passive"))
      (node (ref "SW2") (pin "2") (pinfunction "2_2") (pintype "passive"))
      (node (ref "SW3") (pin "2") (pinfunction "2_2") (pintype "passive"))
      (node (ref "SW4") (pin "2") (pinfunction "2_2") (pintype "passive"))
      (node (ref "SW5") (pin "2") (pinfunction "2_2") (pintype "passive"))
      (node (ref "SW6") (pin "2") (pinfunction "2_2") (pintype "passive"))
      (node (ref "SW7") (pin "2") (pinfunction "2_2") (pintype "passive"))
      (node (ref "T2") (pin "2") (pinfunction "S_2") (pintype "passive"))
      (node (ref "U1") (pin "23") (pinfunction "VSS_23") (pintype "power_in"))
      (node (ref "U1") (pin "35") (pinfunction "VSS_35") (pintype "power_in"))
      (node (ref "U1") (pin "47") (pinfunction "VSS_47") (pintype "power_in"))
      (node (ref "U2") (pin "3") (pinfunction "GND_3") (pintype "power_in"))
      (node (ref "U3") (pin "2") (pinfunction "GND_2") (pintype "power_in"))
      (node (ref "U4") (pin "2") (pinfunction "GND_2") (pintype "power_in"))
      (node (ref "U7") (pin "1") (pinfunction "VSSA_1") (pintype "power_in"))
      (node (ref "U7") (pin "14") (pinfunction "VSS2_14") (pintype "power_in"))
      (node (ref "U7") (pin "18") (pinfunction "VSS1_18") (pintype "power_in"))
      (node (ref "U7") (pin "2") (pinfunction "VBUS2_2") (pintype "power_in"))
      (node (ref "U7") (pin "23") (pinfunction "MODE1_23") (pintype "input"))
      (node (ref "U7") (pin "24") (pinfunction "MODE2_24") (pintype "input"))
      (node (ref "U7") (pin "25") (pinfunction "TREQ_25") (pintype "input"))
      (node (ref "U7") (pin "31") (pinfunction "VSSD_31") (pintype "power_in"))
      (node (ref "U7") (pin "38") (pinfunction "FANIN_38") (pintype "input"))
      (node (ref "U7") (pin "41") (pinfunction "VSSEP_41") (pintype "power_in"))
      (node (ref "U8") (pin "3") (pinfunction "GND_3") (pintype "passive"))
    )
    (net (code "42") (name "Net-(D8-A)") (class "Default")
      (node (ref "D8") (pin "2") (pinfunction "A_2") (pintype "passive"))
      (node (ref "P2") (pin "1") (pinfunction "1_1") (pintype "passive"))
    )
    (net (code "43") (name "Net-(D8-C)") (class "Default")
      (node (ref "C18") (pin "2") (pinfunction "2_2") (pintype "passive"))
      (node (ref "D8") (pin "1") (pinfunction "C_1") (pintype "passive"))
      (node (ref "R20") (pin "2") (pinfunction "2_2") (pintype "passive"))
      (node (ref "U7") (pin "6") (pinfunction "VBUS1_6") (pintype "power_in"))
    )
    (net (code "44") (name "Net-(J1-D+)") (class "Default")
      (node (ref "D7") (pin "2") (pinfunction "2_2") (pintype "passive"))
      (node (ref "J1") (pin "3") (pinfunction "D+_3") (pintype "passive"))
      (node (ref "R13") (pin "1") (pinfunction "1_1") (pintype "passive"))
    )
    (net (code "45") (name "Net-(J1-D-)") (class "Default")
      (node (ref "D7") (pin "3") (pinfunction "3_3") (pintype "passive"))
      (node (ref "J1") (pin "2") (pinfunction "D-_2") (pintype "passive"))
      (node (ref "R12") (pin "1") (pinfunction "1_1") (pintype "passive"))
    )
    (net (code "46") (name "Net-(R22-Pad1)") (class "Default")
      (node (ref "R22") (pin "1") (pinfunction "1_1") (pintype "passive"))
      (node (ref "SW4") (pin "1") (pinfunction "1_1") (pintype "passive"))
    )
    (net (code "47") (name "Net-(R23-Pad1)") (class "Default")
      (node (ref "R23") (pin "1") (pinfunction "1_1") (pintype "passive"))
      (node (ref "SW1") (pin "1") (pinfunction "1_1") (pintype "passive"))
    )
    (net (code "48") (name "Net-(R24-Pad1)") (class "Default")
      (node (ref "R24") (pin "1") (pinfunction "1_1") (pintype "passive"))
      (node (ref "SW5") (pin "1") (pinfunction "1_1") (pintype "passive"))
    )
    (net (code "49") (name "Net-(R25-Pad1)") (class "Default")
      (node (ref "R25") (pin "1") (pinfunction "1_1") (pintype "passive"))
      (node (ref "SW2") (pin "1") (pinfunction "1_1") (pintype "passive"))
    )
    (net (code "50") (name "Net-(R26-Pad1)") (class "Default")
      (node (ref "R26") (pin "1") (pinfunction "1_1") (pintype "passive"))
      (node (ref "SW6") (pin "1") (pinfunction "1_1") (pintype "passive"))
    )
    (net (code "51") (name "Net-(R27-Pad1)") (class "Default")
      (node (ref "R27") (pin "1") (pinfunction "1_1") (pintype "passive"))
      (node (ref "SW3") (pin "1") (pinfunction "1_1") (pintype "passive"))
    )
    (net (code "52") (name "Net-(T1B-G)") (class "Default")
      (node (ref "R1") (pin "2") (pinfunction "2_2") (pintype "passive"))
      (node (ref "T1") (pin "5") (pinfunction "G_5") (pintype "passive"))
      (node (ref "T2") (pin "3") (pinfunction "D_3") (pintype "passive"))
    )
    (net (code "53") (name "Net-(U1A-BOOT0)") (class "Default")
      (node (ref "R15") (pin "1") (pinfunction "1_1") (pintype "passive"))
      (node (ref "U1") (pin "44") (pinfunction "BOOT0_44") (pintype "input"))
    )
    (net (code "54") (name "Net-(U1A-PF0-OSC_IN)") (class "Default")
      (node (ref "C15") (pin "1") (pinfunction "1_1") (pintype "passive"))
      (node (ref "U1") (pin "5") (pinfunction "PF0-OSC_IN_5") (pintype "bidirectional"))
      (node (ref "Y1") (pin "3") (pinfunction "OSC3_3") (pintype "passive"))
    )
    (net (code "55") (name "Net-(U1A-PF1-OSC_OUT)") (class "Default")
      (node (ref "C14") (pin "1") (pinfunction "1_1") (pintype "passive"))
      (node (ref "U1") (pin "6") (pinfunction "PF1-OSC_OUT_6") (pintype "bidirectional"))
      (node (ref "Y1") (pin "1") (pinfunction "OSC1_1") (pintype "passive"))
    )
    (net (code "56") (name "Net-(U4-BYPASS)") (class "Default")
      (node (ref "C2") (pin "1") (pinfunction "1_1") (pintype "passive"))
      (node (ref "U4") (pin "4") (pinfunction "BYPASS_4") (pintype "passive"))
    )
    (net (code "57") (name "Net-(U7-CAV)") (class "Default")
      (node (ref "C17") (pin "1") (pinfunction "1_1") (pintype "passive"))
      (node (ref "U7") (pin "5") (pinfunction "CAV_5") (pintype "bidirectional"))
    )
    (net (code "58") (name "Net-(U7-CCP)") (class "Default")
      (node (ref "C18") (pin "1") (pinfunction "1_1") (pintype "passive"))
      (node (ref "U7") (pin "4") (pinfunction "CCP_4") (pintype "bidirectional"))
    )
    (net (code "59") (name "Net-(U7-CEQ1)") (class "Default")
      (node (ref "C16") (pin "1") (pinfunction "1_1") (pintype "passive"))
      (node (ref "U7") (pin "7") (pinfunction "CEQ1_7") (pintype "bidirectional"))
    )
    (net (code "60") (name "Net-(U7-CEQ2)") (class "Default")
      (node (ref "C16") (pin "2") (pinfunction "2_2") (pintype "passive"))
      (node (ref "U7") (pin "8") (pinfunction "CEQ2_8") (pintype "bidirectional"))
    )
    (net (code "61") (name "Net-(U7-SCK{slash}UC2)") (class "Default")
      (node (ref "P4") (pin "2") (pinfunction "2_2") (pintype "passive"))
      (node (ref "U7") (pin "29") (pinfunction "SCK/UC2_29") (pintype "bidirectional"))
    )
    (net (code "62") (name "Net-(U7-TXO)") (class "Default")
      (node (ref "R20") (pin "1") (pinfunction "1_1") (pintype "passive"))
      (node (ref "U7") (pin "3") (pinfunction "TXO_3") (pintype "output"))
    )
    (net (code "63") (name "Net-(U7-VDD1M)") (class "Default")
      (node (ref "L1") (pin "2") (pinfunction "2_2") (pintype "passive"))
      (node (ref "R21") (pin "2") (pinfunction "2_2") (pintype "passive"))
      (node (ref "U7") (pin "20") (pinfunction "VDD1M_20") (pintype "input"))
    )
    (net (code "64") (name "Net-(U7-VSW1)") (class "Default")
      (node (ref "L1") (pin "1") (pinfunction "1_1") (pintype "passive"))
      (node (ref "U7") (pin "17") (pinfunction "VSW1_17") (pintype "output"))
    )
    (net (code "65") (name "VUSB") (class "Default")
      (node (ref "D7") (pin "4") (pinfunction "4_4") (pintype "passive"))
      (node (ref "J1") (pin "1") (pinfunction "VCC_1") (pintype "passive"))
      (node (ref "R11") (pin "1") (pinfunction "1_1") (pintype "passive"))
    )
    (net (code "66") (name "unconnected-(J1-ID-Pad4)") (class "Default")
      (node (ref "J1") (pin "4") (pinfunction "ID_4") (pintype "passive"))
    )
    (net (code "67") (name "unconnected-(U1A-PB1-Pad19)") (class "Default")
      (node (ref "U1") (pin "19") (pinfunction "PB1_19") (pintype "bidirectional"))
    )
    (net (code "68") (name "unconnected-(U1A-PB2-Pad20)") (class "Default")
      (node (ref "U1") (pin "20") (pinfunction "PB2_20") (pintype "bidirectional"))
    )
    (net (code "69") (name "unconnected-(U1A-PB4-Pad40)") (class "Default")
      (node (ref "U1") (pin "40") (pinfunction "PB4_40") (pintype "bidirectional"))
    )
    (net (code "70") (name "unconnected-(U1A-PB5-Pad41)") (class "Default")
      (node (ref "U1") (pin "41") (pinfunction "PB5_41") (pintype "bidirectional"))
    )
    (net (code "71") (name "unconnected-(U1A-PB8-Pad45)") (class "Default")
      (node (ref "U1") (pin "45") (pinfunction "PB8_45") (pintype "bidirectional"))
    )
    (net (code "72") (name "unconnected-(U1A-PB9-Pad46)") (class "Default")
      (node (ref "U1") (pin "46") (pinfunction "PB9_46") (pintype "bidirectional"))
    )
    (net (code "73") (name "unconnected-(U1A-PC15-OSC32_OUT-Pad4)") (class "Default")
      (node (ref "U1") (pin "4") (pinfunction "PC15-OSC32_OUT_4") (pintype "bidirectional"))
    )
    (net (code "74") (name "unconnected-(U3-N.C.-Pad3)") (class "Default")
      (node (ref "U3") (pin "3") (pinfunction "N.C._3") (pintype "passive"))
    )
    (net (code "75") (name "unconnected-(U3-N.C.-Pad4)") (class "Default")
      (node (ref "U3") (pin "4") (pinfunction "N.C._4") (pintype "passive"))
    )
    (net (code "76") (name "unconnected-(U7-ANAOUT-Pad39)") (class "Default")
      (node (ref "U7") (pin "39") (pinfunction "ANAOUT_39") (pintype "output+no_connect"))
    )
    (net (code "77") (name "unconnected-(U7-TRIG-Pad22)") (class "Default")
      (node (ref "U7") (pin "22") (pinfunction "TRIG_22") (pintype "output+no_connect"))
    )
    (net (code "78") (name "unconnected-(U7-VDD2-Pad13)") (class "Default")
      (node (ref "U7") (pin "13") (pinfunction "VDD2_13") (pintype "input+no_connect"))
    )
    (net (code "79") (name "unconnected-(U7-VDD2MC-Pad12)") (class "Default")
      (node (ref "U7") (pin "12") (pinfunction "VDD2MC_12") (pintype "input+no_connect"))
    )
    (net (code "80") (name "unconnected-(U7-VSW2-Pad15)") (class "Default")
      (node (ref "U7") (pin "15") (pinfunction "VSW2_15") (pintype "output+no_connect"))
    )
    (net (code "81") (name "unconnected-(U7-XCLK-Pad32)") (class "Default")
      (node (ref "U7") (pin "32") (pinfunction "XCLK_32") (pintype "output+no_connect"))
    )
    (net (code "82") (name "unconnected-(U7-XTAL2-Pad34)") (class "Default")
      (node (ref "U7") (pin "34") (pinfunction "XTAL2_34") (pintype "bidirectional+no_connect"))
    )
    (net (code "83") (name "unconnected-(U8-ADDR-Pad2)") (class "Default")
      (node (ref "U8") (pin "2") (pinfunction "ADDR_2") (pintype "input+no_connect"))
    )
    (net (code "84") (name "unconnected-(Y1-GND1-Pad2)") (class "Default")
      (node (ref "Y1") (pin "2") (pinfunction "GND1_2") (pintype "power_in+no_connect"))
    )
    (net (code "85") (name "unconnected-(Y1-GND2-Pad4)") (class "Default")
      (node (ref "Y1") (pin "4") (pinfunction "GND2_4") (pintype "power_in+no_connect"))
    )
  )
)
